# FilterBoard_Schematic.net
KiCad netlist of a schematic drawn in Altium Designer
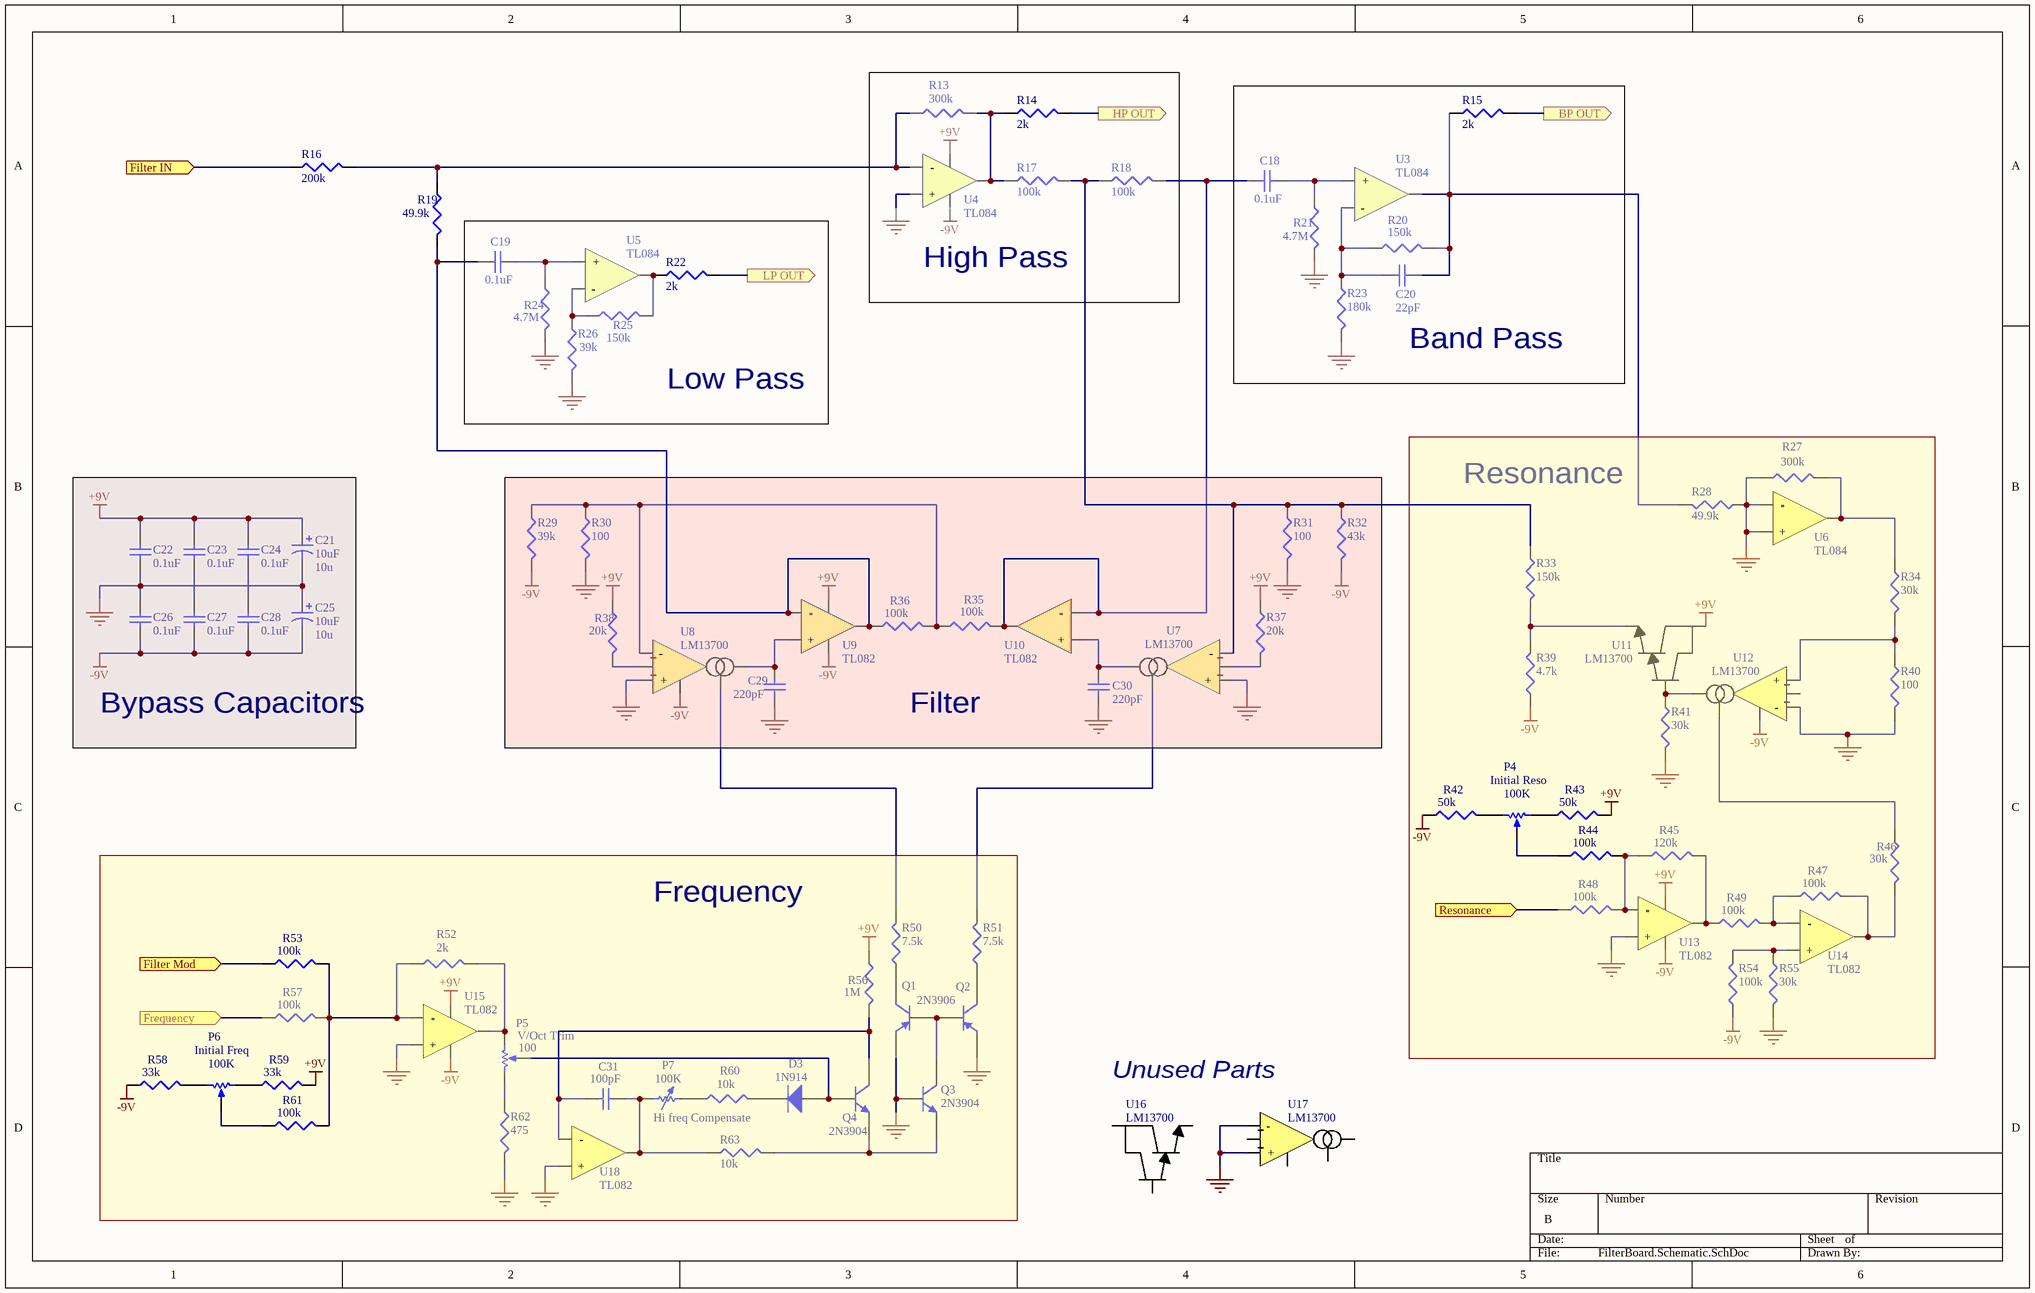
[diagram p0: FilterBoard.Schematic.SchDoc]

(export (version "E")
  (design (tool "Eeschema 10.0.6"))
  (components
    (comp (ref "C18")
      (value "0.1uF")
      (footprint "CAPC1608N")
      (description "Capacitor (Semiconductor SIM Model)")
      (fields (field (name "PUBLISHER") "Altium Limited"))
      (libsource (lib "Miscellaneous Devices") (part "Cap Semi"))
    )
    (comp (ref "C19")
      (value "0.1uF")
      (footprint "CAPC1608N")
      (description "Capacitor (Semiconductor SIM Model)")
      (fields (field (name "PUBLISHER") "Altium Limited"))
      (libsource (lib "Miscellaneous Devices") (part "Cap Semi"))
    )
    (comp (ref "C20")
      (value "22pF")
      (footprint "CAPC1608N")
      (description "Capacitor (Semiconductor SIM Model)")
      (fields (field (name "PUBLISHER") "Altium Limited"))
      (libsource (lib "Miscellaneous Devices") (part "Cap Semi"))
    )
    (comp (ref "C21")
      (value "10uF")
      (footprint "RB7.6-15")
      (description "Polarized Capacitor (Radial)")
      (fields (field (name "ALTIUM_VALUE") "10u") (field (name "PUBLISHER") "Altium Limited"))
      (libsource (lib "Miscellaneous Devices") (part "Cap Pol1"))
    )
    (comp (ref "C22")
      (value "0.1uF")
      (footprint "CAPC1608N")
      (description "Capacitor (Semiconductor SIM Model)")
      (fields (field (name "PUBLISHER") "Altium Limited"))
      (libsource (lib "Miscellaneous Devices") (part "Cap Semi"))
    )
    (comp (ref "C23")
      (value "0.1uF")
      (footprint "CAPC1608N")
      (description "Capacitor (Semiconductor SIM Model)")
      (fields (field (name "PUBLISHER") "Altium Limited"))
      (libsource (lib "Miscellaneous Devices") (part "Cap Semi"))
    )
    (comp (ref "C24")
      (value "0.1uF")
      (footprint "CAPC1608N")
      (description "Capacitor (Semiconductor SIM Model)")
      (fields (field (name "PUBLISHER") "Altium Limited"))
      (libsource (lib "Miscellaneous Devices") (part "Cap Semi"))
    )
    (comp (ref "C25")
      (value "10uF")
      (footprint "RB7.6-15")
      (description "Polarized Capacitor (Radial)")
      (fields (field (name "ALTIUM_VALUE") "10u") (field (name "PUBLISHER") "Altium Limited"))
      (libsource (lib "Miscellaneous Devices") (part "Cap Pol1"))
    )
    (comp (ref "C26")
      (value "0.1uF")
      (footprint "CAPC1608N")
      (description "Capacitor (Semiconductor SIM Model)")
      (fields (field (name "PUBLISHER") "Altium Limited"))
      (libsource (lib "Miscellaneous Devices") (part "Cap Semi"))
    )
    (comp (ref "C27")
      (value "0.1uF")
      (footprint "CAPC1608N")
      (description "Capacitor (Semiconductor SIM Model)")
      (fields (field (name "PUBLISHER") "Altium Limited"))
      (libsource (lib "Miscellaneous Devices") (part "Cap Semi"))
    )
    (comp (ref "C28")
      (value "0.1uF")
      (footprint "CAPC1608N")
      (description "Capacitor (Semiconductor SIM Model)")
      (fields (field (name "PUBLISHER") "Altium Limited"))
      (libsource (lib "Miscellaneous Devices") (part "Cap Semi"))
    )
    (comp (ref "C29")
      (value "220pF")
      (footprint "CAPC1608N")
      (description "Capacitor (Semiconductor SIM Model)")
      (fields (field (name "PUBLISHER") "Altium Limited"))
      (libsource (lib "Miscellaneous Devices") (part "Cap Semi"))
    )
    (comp (ref "C30")
      (value "220pF")
      (footprint "CAPC1608N")
      (description "Capacitor (Semiconductor SIM Model)")
      (fields (field (name "PUBLISHER") "Altium Limited"))
      (libsource (lib "Miscellaneous Devices") (part "Cap Semi"))
    )
    (comp (ref "C31")
      (value "100pF")
      (footprint "CAPC1608N")
      (description "Capacitor (Semiconductor SIM Model)")
      (fields (field (name "PUBLISHER") "Altium Limited"))
      (libsource (lib "Miscellaneous Devices") (part "Cap Semi"))
    )
    (comp (ref "D3")
      (value "1N914")
      (footprint "1N914")
      (description "1 Amp General Purpose Rectifier")
      (fields (field (name "PUBLISHER") "Altium Limited"))
      (libsource (lib "Miscellaneous Devices") (part "Diode 1N4001"))
    )
    (comp (ref "P4")
      (value "Initial Reso")
      (footprint "VR5")
      (description "Potentiometer")
      (fields (field (name "ALTIUM_VALUE") "100K") (field (name "PUBLISHER") "Altium Limited"))
      (libsource (lib "Miscellaneous Devices") (part "RPot"))
    )
    (comp (ref "P5")
      (value "V/Oct Trim")
      (footprint "VR5")
      (description "Potentiometer")
      (fields (field (name "ALTIUM_VALUE") "100") (field (name "PUBLISHER") "Altium Limited"))
      (libsource (lib "Miscellaneous Devices") (part "RPot"))
    )
    (comp (ref "P6")
      (value "Initial Freq")
      (footprint "VR5")
      (description "Potentiometer")
      (fields (field (name "ALTIUM_VALUE") "100K") (field (name "PUBLISHER") "Altium Limited"))
      (libsource (lib "Miscellaneous Devices") (part "RPot"))
    )
    (comp (ref "P7")
      (value "Hi freq Compensate")
      (footprint "CAPC1608N")
      (description "Variable Resistor")
      (fields (field (name "ALTIUM_VALUE") "100K") (field (name "PUBLISHER") "Altium Limited"))
      (libsource (lib "Miscellaneous Devices") (part "Res Adj1"))
    )
    (comp (ref "Q1")
      (value "2N3906")
      (footprint "2N3906")
      (description "PNP General Purpose Amplifier")
      (fields (field (name "PUBLISHER") "Altium Limited"))
      (libsource (lib "Miscellaneous Devices") (part "2N3906"))
    )
    (comp (ref "Q2")
      (value "2N3906")
      (footprint "2N3906")
      (description "PNP General Purpose Amplifier")
      (fields (field (name "PUBLISHER") "Altium Limited"))
      (libsource (lib "Miscellaneous Devices") (part "2N3906"))
    )
    (comp (ref "Q3")
      (value "2N3904")
      (footprint "TO-92A")
      (description "NPN General Purpose Amplifier")
      (fields (field (name "PUBLISHER") "Altium Limited"))
      (libsource (lib "Miscellaneous Devices") (part "2N3904"))
    )
    (comp (ref "Q4")
      (value "2N3904")
      (footprint "TO-92A")
      (description "NPN General Purpose Amplifier")
      (fields (field (name "PUBLISHER") "Altium Limited"))
      (libsource (lib "Miscellaneous Devices") (part "2N3904"))
    )
    (comp (ref "R13")
      (value "300k")
      (footprint "CAPC1608N")
      (description "Resistor")
      (fields (field (name "PUBLISHER") "Altium Limited"))
      (libsource (lib "Miscellaneous Devices") (part "Res3"))
    )
    (comp (ref "R14")
      (value "2k")
      (footprint "CAPC1608N")
      (description "Resistor")
      (fields (field (name "PUBLISHER") "Altium Limited"))
      (libsource (lib "Miscellaneous Devices") (part "Res3"))
    )
    (comp (ref "R15")
      (value "2k")
      (footprint "CAPC1608N")
      (description "Resistor")
      (fields (field (name "PUBLISHER") "Altium Limited"))
      (libsource (lib "Miscellaneous Devices") (part "Res3"))
    )
    (comp (ref "R16")
      (value "200k")
      (footprint "CAPC1608N")
      (description "Resistor")
      (fields (field (name "PUBLISHER") "Altium Limited"))
      (libsource (lib "Miscellaneous Devices") (part "Res3"))
    )
    (comp (ref "R17")
      (value "100k")
      (footprint "CAPC1608N")
      (description "Resistor")
      (fields (field (name "PUBLISHER") "Altium Limited"))
      (libsource (lib "Miscellaneous Devices") (part "Res3"))
    )
    (comp (ref "R18")
      (value "100k")
      (footprint "CAPC1608N")
      (description "Resistor")
      (fields (field (name "PUBLISHER") "Altium Limited"))
      (libsource (lib "Miscellaneous Devices") (part "Res3"))
    )
    (comp (ref "R19")
      (value "49.9k")
      (footprint "CAPC1608N")
      (description "Resistor")
      (fields (field (name "PUBLISHER") "Altium Limited"))
      (libsource (lib "Miscellaneous Devices") (part "Res3"))
    )
    (comp (ref "R20")
      (value "150k")
      (footprint "CAPC1608N")
      (description "Resistor")
      (fields (field (name "PUBLISHER") "Altium Limited"))
      (libsource (lib "Miscellaneous Devices") (part "Res3"))
    )
    (comp (ref "R21")
      (value "4.7M")
      (footprint "CAPC1608N")
      (description "Resistor")
      (fields (field (name "PUBLISHER") "Altium Limited"))
      (libsource (lib "Miscellaneous Devices") (part "Res3"))
    )
    (comp (ref "R22")
      (value "2k")
      (footprint "CAPC1608N")
      (description "Resistor")
      (fields (field (name "PUBLISHER") "Altium Limited"))
      (libsource (lib "Miscellaneous Devices") (part "Res3"))
    )
    (comp (ref "R23")
      (value "180k")
      (footprint "CAPC1608N")
      (description "Resistor")
      (fields (field (name "PUBLISHER") "Altium Limited"))
      (libsource (lib "Miscellaneous Devices") (part "Res3"))
    )
    (comp (ref "R24")
      (value "4.7M")
      (footprint "CAPC1608N")
      (description "Resistor")
      (fields (field (name "PUBLISHER") "Altium Limited"))
      (libsource (lib "Miscellaneous Devices") (part "Res3"))
    )
    (comp (ref "R25")
      (value "150k")
      (footprint "CAPC1608N")
      (description "Resistor")
      (fields (field (name "PUBLISHER") "Altium Limited"))
      (libsource (lib "Miscellaneous Devices") (part "Res3"))
    )
    (comp (ref "R26")
      (value "39k")
      (footprint "CAPC1608N")
      (description "Resistor")
      (fields (field (name "PUBLISHER") "Altium Limited"))
      (libsource (lib "Miscellaneous Devices") (part "Res3"))
    )
    (comp (ref "R27")
      (value "300k")
      (footprint "CAPC1608N")
      (description "Resistor")
      (fields (field (name "PUBLISHER") "Altium Limited"))
      (libsource (lib "Miscellaneous Devices") (part "Res3"))
    )
    (comp (ref "R28")
      (value "49.9k")
      (footprint "CAPC1608N")
      (description "Resistor")
      (fields (field (name "PUBLISHER") "Altium Limited"))
      (libsource (lib "Miscellaneous Devices") (part "Res3"))
    )
    (comp (ref "R29")
      (value "39k")
      (footprint "CAPC1608N")
      (description "Resistor")
      (fields (field (name "PUBLISHER") "Altium Limited"))
      (libsource (lib "Miscellaneous Devices") (part "Res3"))
    )
    (comp (ref "R30")
      (value "100")
      (footprint "CAPC1608N")
      (description "Resistor")
      (fields (field (name "PUBLISHER") "Altium Limited"))
      (libsource (lib "Miscellaneous Devices") (part "Res3"))
    )
    (comp (ref "R31")
      (value "100")
      (footprint "CAPC1608N")
      (description "Resistor")
      (fields (field (name "PUBLISHER") "Altium Limited"))
      (libsource (lib "Miscellaneous Devices") (part "Res3"))
    )
    (comp (ref "R32")
      (value "43k")
      (footprint "CAPC1608N")
      (description "Resistor")
      (fields (field (name "PUBLISHER") "Altium Limited"))
      (libsource (lib "Miscellaneous Devices") (part "Res3"))
    )
    (comp (ref "R33")
      (value "150k")
      (footprint "CAPC1608N")
      (description "Resistor")
      (fields (field (name "PUBLISHER") "Altium Limited"))
      (libsource (lib "Miscellaneous Devices") (part "Res3"))
    )
    (comp (ref "R34")
      (value "30k")
      (footprint "CAPC1608N")
      (description "Resistor")
      (fields (field (name "PUBLISHER") "Altium Limited"))
      (libsource (lib "Miscellaneous Devices") (part "Res3"))
    )
    (comp (ref "R35")
      (value "100k")
      (footprint "CAPC1608N")
      (description "Resistor")
      (fields (field (name "PUBLISHER") "Altium Limited"))
      (libsource (lib "Miscellaneous Devices") (part "Res3"))
    )
    (comp (ref "R36")
      (value "100k")
      (footprint "CAPC1608N")
      (description "Resistor")
      (fields (field (name "PUBLISHER") "Altium Limited"))
      (libsource (lib "Miscellaneous Devices") (part "Res3"))
    )
    (comp (ref "R37")
      (value "20k")
      (footprint "CAPC1608N")
      (description "Resistor")
      (fields (field (name "PUBLISHER") "Altium Limited"))
      (libsource (lib "Miscellaneous Devices") (part "Res3"))
    )
    (comp (ref "R38")
      (value "20k")
      (footprint "CAPC1608N")
      (description "Resistor")
      (fields (field (name "PUBLISHER") "Altium Limited"))
      (libsource (lib "Miscellaneous Devices") (part "Res3"))
    )
    (comp (ref "R39")
      (value "4.7k")
      (footprint "CAPC1608N")
      (description "Resistor")
      (fields (field (name "PUBLISHER") "Altium Limited"))
      (libsource (lib "Miscellaneous Devices") (part "Res3"))
    )
    (comp (ref "R40")
      (value "100")
      (footprint "CAPC1608N")
      (description "Resistor")
      (fields (field (name "PUBLISHER") "Altium Limited"))
      (libsource (lib "Miscellaneous Devices") (part "Res3"))
    )
    (comp (ref "R41")
      (value "30k")
      (footprint "CAPC1608N")
      (description "Resistor")
      (fields (field (name "PUBLISHER") "Altium Limited"))
      (libsource (lib "Miscellaneous Devices") (part "Res3"))
    )
    (comp (ref "R42")
      (value "50k")
      (footprint "CAPC1608N")
      (description "Resistor")
      (fields (field (name "PUBLISHER") "Altium Limited"))
      (libsource (lib "Miscellaneous Devices") (part "Res3"))
    )
    (comp (ref "R43")
      (value "50k")
      (footprint "CAPC1608N")
      (description "Resistor")
      (fields (field (name "PUBLISHER") "Altium Limited"))
      (libsource (lib "Miscellaneous Devices") (part "Res3"))
    )
    (comp (ref "R44")
      (value "100k")
      (footprint "CAPC1608N")
      (description "Resistor")
      (fields (field (name "PUBLISHER") "Altium Limited"))
      (libsource (lib "Miscellaneous Devices") (part "Res3"))
    )
    (comp (ref "R45")
      (value "120k")
      (footprint "CAPC1608N")
      (description "Resistor")
      (fields (field (name "PUBLISHER") "Altium Limited"))
      (libsource (lib "Miscellaneous Devices") (part "Res3"))
    )
    (comp (ref "R46")
      (value "30k")
      (footprint "CAPC1608N")
      (description "Resistor")
      (fields (field (name "PUBLISHER") "Altium Limited"))
      (libsource (lib "Miscellaneous Devices") (part "Res3"))
    )
    (comp (ref "R47")
      (value "100k")
      (footprint "CAPC1608N")
      (description "Resistor")
      (fields (field (name "PUBLISHER") "Altium Limited"))
      (libsource (lib "Miscellaneous Devices") (part "Res3"))
    )
    (comp (ref "R48")
      (value "100k")
      (footprint "CAPC1608N")
      (description "Resistor")
      (fields (field (name "PUBLISHER") "Altium Limited"))
      (libsource (lib "Miscellaneous Devices") (part "Res3"))
    )
    (comp (ref "R49")
      (value "100k")
      (footprint "CAPC1608N")
      (description "Resistor")
      (fields (field (name "PUBLISHER") "Altium Limited"))
      (libsource (lib "Miscellaneous Devices") (part "Res3"))
    )
    (comp (ref "R50")
      (value "7.5k")
      (footprint "CAPC1608N")
      (description "Resistor")
      (fields (field (name "PUBLISHER") "Altium Limited"))
      (libsource (lib "Miscellaneous Devices") (part "Res3"))
    )
    (comp (ref "R51")
      (value "7.5k")
      (footprint "CAPC1608N")
      (description "Resistor")
      (fields (field (name "PUBLISHER") "Altium Limited"))
      (libsource (lib "Miscellaneous Devices") (part "Res3"))
    )
    (comp (ref "R52")
      (value "2k")
      (footprint "CAPC1608N")
      (description "Resistor")
      (fields (field (name "PUBLISHER") "Altium Limited"))
      (libsource (lib "Miscellaneous Devices") (part "Res3"))
    )
    (comp (ref "R53")
      (value "100k")
      (footprint "CAPC1608N")
      (description "Resistor")
      (fields (field (name "PUBLISHER") "Altium Limited"))
      (libsource (lib "Miscellaneous Devices") (part "Res3"))
    )
    (comp (ref "R54")
      (value "100k")
      (footprint "CAPC1608N")
      (description "Resistor")
      (fields (field (name "PUBLISHER") "Altium Limited"))
      (libsource (lib "Miscellaneous Devices") (part "Res3"))
    )
    (comp (ref "R55")
      (value "30k")
      (footprint "CAPC1608N")
      (description "Resistor")
      (fields (field (name "PUBLISHER") "Altium Limited"))
      (libsource (lib "Miscellaneous Devices") (part "Res3"))
    )
    (comp (ref "R56")
      (value "1M")
      (footprint "CAPC1608N")
      (description "Resistor")
      (fields (field (name "PUBLISHER") "Altium Limited"))
      (libsource (lib "Miscellaneous Devices") (part "Res3"))
    )
    (comp (ref "R57")
      (value "100k")
      (footprint "CAPC1608N")
      (description "Resistor")
      (fields (field (name "PUBLISHER") "Altium Limited"))
      (libsource (lib "Miscellaneous Devices") (part "Res3"))
    )
    (comp (ref "R58")
      (value "33k")
      (footprint "CAPC1608N")
      (description "Resistor")
      (fields (field (name "PUBLISHER") "Altium Limited"))
      (libsource (lib "Miscellaneous Devices") (part "Res3"))
    )
    (comp (ref "R59")
      (value "33k")
      (footprint "CAPC1608N")
      (description "Resistor")
      (fields (field (name "PUBLISHER") "Altium Limited"))
      (libsource (lib "Miscellaneous Devices") (part "Res3"))
    )
    (comp (ref "R60")
      (value "10k")
      (footprint "CAPC1608N")
      (description "Resistor")
      (fields (field (name "PUBLISHER") "Altium Limited"))
      (libsource (lib "Miscellaneous Devices") (part "Res3"))
    )
    (comp (ref "R61")
      (value "100k")
      (footprint "CAPC1608N")
      (description "Resistor")
      (fields (field (name "PUBLISHER") "Altium Limited"))
      (libsource (lib "Miscellaneous Devices") (part "Res3"))
    )
    (comp (ref "R62")
      (value "475")
      (footprint "CAPC1608N")
      (description "Resistor")
      (fields (field (name "PUBLISHER") "Altium Limited"))
      (libsource (lib "Miscellaneous Devices") (part "Res3"))
    )
    (comp (ref "R63")
      (value "10k")
      (footprint "CAPC1608N")
      (description "Resistor")
      (fields (field (name "PUBLISHER") "Altium Limited"))
      (libsource (lib "Miscellaneous Devices") (part "Res3"))
    )
    (comp (ref "U3") (value "TL084") (libsource (lib "") (part "TL084_1")))
    (comp (ref "U4") (value "TL084") (libsource (lib "SynthyTwo.Components") (part "TL084")))
    (comp (ref "U5") (value "TL084") (libsource (lib "") (part "TL084_1")))
    (comp (ref "U6") (value "TL084") (libsource (lib "") (part "TL084_2")))
    (comp (ref "U7")
      (value "LM13700")
      (footprint "LM13700")
      (libsource (lib "SynthyTwo.Components") (part "LM13700"))
    )
    (comp (ref "U8")
      (value "LM13700")
      (footprint "LM13700")
      (libsource (lib "SynthyTwo.Components") (part "LM13700"))
    )
    (comp (ref "U9")
      (value "TL082")
      (footprint "TL084")
      (libsource (lib "SynthyTwo.Components") (part "TL082"))
    )
    (comp (ref "U10") (value "TL082") (footprint "TL084") (libsource (lib "") (part "TL082_1")))
    (comp (ref "U11") (value "LM13700") (libsource (lib "SynthyTwo.Components") (part "LM13700_1")))
    (comp (ref "U12")
      (value "LM13700")
      (footprint "LM13700")
      (libsource (lib "SynthyTwo.Components") (part "LM13700"))
    )
    (comp (ref "U13")
      (value "TL082")
      (footprint "TL084")
      (libsource (lib "SynthyTwo.Components") (part "TL082"))
    )
    (comp (ref "U14") (value "TL082") (footprint "TL084") (libsource (lib "") (part "TL082_1")))
    (comp (ref "U15")
      (value "TL082")
      (footprint "TL084")
      (libsource (lib "SynthyTwo.Components") (part "TL082"))
    )
    (comp (ref "U16") (value "LM13700") (libsource (lib "SynthyTwo.Components") (part "LM13700_1")))
    (comp (ref "U17")
      (value "LM13700")
      (footprint "LM13700")
      (libsource (lib "SynthyTwo.Components") (part "LM13700"))
    )
    (comp (ref "U18") (value "TL082") (footprint "TL084") (libsource (lib "") (part "TL082_1")))
  )
  (nets
    (net (code "1") (name "+9V") (class "Default")
      (node (ref "C21") (pin "1") (pinfunction "1_1") (pintype "passive"))
      (node (ref "C22") (pin "2") (pinfunction "2_2") (pintype "passive"))
      (node (ref "C23") (pin "2") (pinfunction "2_2") (pintype "passive"))
      (node (ref "C24") (pin "2") (pinfunction "2_2") (pintype "passive"))
      (node (ref "R37") (pin "1") (pinfunction "1_1") (pintype "passive"))
      (node (ref "R38") (pin "1") (pinfunction "1_1") (pintype "passive"))
      (node (ref "R43") (pin "2") (pinfunction "2_2") (pintype "passive"))
      (node (ref "R56") (pin "1") (pinfunction "1_1") (pintype "passive"))
      (node (ref "R59") (pin "2") (pinfunction "2_2") (pintype "passive"))
      (node (ref "U11") (pin "11") (pinfunction "V+_11") (pintype "passive"))
      (node (ref "U13") (pin "8") (pinfunction "VCC+_8") (pintype "passive"))
      (node (ref "U15") (pin "8") (pinfunction "VCC+_8") (pintype "passive"))
      (node (ref "U4") (pin "4") (pinfunction "VCC+_4") (pintype "passive"))
      (node (ref "U9") (pin "8") (pinfunction "VCC+_8") (pintype "passive"))
    )
    (net (code "2") (name "-9V") (class "Default")
      (node (ref "C25") (pin "2") (pinfunction "2_2") (pintype "passive"))
      (node (ref "C26") (pin "1") (pinfunction "1_1") (pintype "passive"))
      (node (ref "C27") (pin "1") (pinfunction "1_1") (pintype "passive"))
      (node (ref "C28") (pin "1") (pinfunction "1_1") (pintype "passive"))
      (node (ref "R29") (pin "2") (pinfunction "2_2") (pintype "passive"))
      (node (ref "R32") (pin "2") (pinfunction "2_2") (pintype "passive"))
      (node (ref "R39") (pin "1") (pinfunction "1_1") (pintype "passive"))
      (node (ref "R42") (pin "1") (pinfunction "1_1") (pintype "passive"))
      (node (ref "R54") (pin "1") (pinfunction "1_1") (pintype "passive"))
      (node (ref "R58") (pin "1") (pinfunction "1_1") (pintype "passive"))
      (node (ref "U12") (pin "6") (pinfunction "VCC-_6") (pintype "passive"))
      (node (ref "U13") (pin "4") (pinfunction "VCC-_4") (pintype "passive"))
      (node (ref "U15") (pin "4") (pinfunction "VCC-_4") (pintype "passive"))
      (node (ref "U4") (pin "11") (pinfunction "VCC-_11") (pintype "passive"))
      (node (ref "U8") (pin "6") (pinfunction "VCC-_6") (pintype "passive"))
      (node (ref "U9") (pin "4") (pinfunction "VCC-_4") (pintype "passive"))
    )
    (net (code "3") (name "/BP OUT") (class "Default")
      (node (ref "R15") (pin "2") (pinfunction "2_2") (pintype "passive"))
    )
    (net (code "4") (name "/Filter IN") (class "Default")
      (node (ref "R16") (pin "1") (pinfunction "1_1") (pintype "passive"))
    )
    (net (code "5") (name "/Filter Mod") (class "Default")
      (node (ref "R53") (pin "1") (pinfunction "1_1") (pintype "passive"))
    )
    (net (code "6") (name "/Frequency") (class "Default")
      (node (ref "R57") (pin "1") (pinfunction "1_1") (pintype "passive"))
    )
    (net (code "7") (name "/HP OUT") (class "Default")
      (node (ref "R14") (pin "2") (pinfunction "2_2") (pintype "passive"))
    )
    (net (code "8") (name "/LP OUT") (class "Default")
      (node (ref "R22") (pin "2") (pinfunction "2_2") (pintype "passive"))
    )
    (net (code "9") (name "/Resonance") (class "Default")
      (node (ref "R48") (pin "1") (pinfunction "1_1") (pintype "passive"))
    )
    (net (code "10") (name "GND") (class "Default")
      (node (ref "C21") (pin "2") (pinfunction "2_2") (pintype "passive"))
      (node (ref "C22") (pin "1") (pinfunction "1_1") (pintype "passive"))
      (node (ref "C25") (pin "1") (pinfunction "1_1") (pintype "passive"))
      (node (ref "C26") (pin "2") (pinfunction "2_2") (pintype "passive"))
      (node (ref "C29") (pin "1") (pinfunction "1_1") (pintype "passive"))
      (node (ref "C30") (pin "1") (pinfunction "1_1") (pintype "passive"))
      (node (ref "Q1") (pin "1") (pinfunction "E_1") (pintype "passive"))
      (node (ref "Q2") (pin "1") (pinfunction "E_1") (pintype "passive"))
      (node (ref "Q3") (pin "2") (pinfunction "B_2") (pintype "passive"))
      (node (ref "R21") (pin "2") (pinfunction "2_2") (pintype "passive"))
      (node (ref "R23") (pin "2") (pinfunction "2_2") (pintype "passive"))
      (node (ref "R24") (pin "2") (pinfunction "2_2") (pintype "passive"))
      (node (ref "R26") (pin "2") (pinfunction "2_2") (pintype "passive"))
      (node (ref "R27") (pin "1") (pinfunction "1_1") (pintype "passive"))
      (node (ref "R28") (pin "1") (pinfunction "1_1") (pintype "passive"))
      (node (ref "R30") (pin "2") (pinfunction "2_2") (pintype "passive"))
      (node (ref "R31") (pin "2") (pinfunction "2_2") (pintype "passive"))
      (node (ref "R40") (pin "2") (pinfunction "2_2") (pintype "passive"))
      (node (ref "R41") (pin "2") (pinfunction "2_2") (pintype "passive"))
      (node (ref "R55") (pin "2") (pinfunction "2_2") (pintype "passive"))
      (node (ref "R62") (pin "2") (pinfunction "2_2") (pintype "passive"))
      (node (ref "U12") (pin "3") (pinfunction "+_3") (pintype "passive"))
      (node (ref "U13") (pin "3") (pinfunction "+_3") (pintype "passive"))
      (node (ref "U15") (pin "3") (pinfunction "+_3") (pintype "passive"))
      (node (ref "U17") (pin "3") (pinfunction "+_3") (pintype "passive"))
      (node (ref "U17") (pin "4") (pinfunction "-_4") (pintype "passive"))
      (node (ref "U18") (pin "5") (pinfunction "+_5") (pintype "passive"))
      (node (ref "U4") (pin "3") (pinfunction "+_3") (pintype "passive"))
      (node (ref "U6") (pin "12") (pinfunction "-_12") (pintype "passive"))
      (node (ref "U6") (pin "13") (pinfunction "+_13") (pintype "passive"))
      (node (ref "U7") (pin "3") (pinfunction "+_3") (pintype "passive"))
      (node (ref "U8") (pin "3") (pinfunction "+_3") (pintype "passive"))
    )
    (net (code "11") (name "Net-(C23-Pad1)") (class "Default")
      (node (ref "C23") (pin "1") (pinfunction "1_1") (pintype "passive"))
      (node (ref "C27") (pin "2") (pinfunction "2_2") (pintype "passive"))
    )
    (net (code "12") (name "Net-(C24-Pad1)") (class "Default")
      (node (ref "C24") (pin "1") (pinfunction "1_1") (pintype "passive"))
      (node (ref "C28") (pin "2") (pinfunction "2_2") (pintype "passive"))
    )
    (net (code "13") (name "Net-(D3-A)") (class "Default")
      (node (ref "D3") (pin "1") (pinfunction "A_1") (pintype "passive"))
      (node (ref "P5") (pin "3") (pinfunction "TAP_3") (pintype "passive"))
      (node (ref "Q4") (pin "2") (pinfunction "B_2") (pintype "passive"))
    )
    (net (code "14") (name "Net-(D3-K)") (class "Default")
      (node (ref "D3") (pin "2") (pinfunction "K_2") (pintype "passive"))
      (node (ref "R60") (pin "2") (pinfunction "2_2") (pintype "passive"))
    )
    (net (code "15") (name "Net-(P4-BOT)") (class "Default")
      (node (ref "P4") (pin "2") (pinfunction "BOT_2") (pintype "passive"))
      (node (ref "R42") (pin "2") (pinfunction "2_2") (pintype "passive"))
    )
    (net (code "16") (name "Net-(P4-TAP)") (class "Default")
      (node (ref "P4") (pin "3") (pinfunction "TAP_3") (pintype "passive"))
      (node (ref "R44") (pin "1") (pinfunction "1_1") (pintype "passive"))
    )
    (net (code "17") (name "Net-(P4-TOP)") (class "Default")
      (node (ref "P4") (pin "1") (pinfunction "TOP_1") (pintype "passive"))
      (node (ref "R43") (pin "1") (pinfunction "1_1") (pintype "passive"))
    )
    (net (code "18") (name "Net-(P5-BOT)") (class "Default")
      (node (ref "P5") (pin "2") (pinfunction "BOT_2") (pintype "passive"))
      (node (ref "R62") (pin "1") (pinfunction "1_1") (pintype "passive"))
    )
    (net (code "19") (name "Net-(P5-TOP)") (class "Default")
      (node (ref "P5") (pin "1") (pinfunction "TOP_1") (pintype "passive"))
      (node (ref "R52") (pin "2") (pinfunction "2_2") (pintype "passive"))
      (node (ref "U15") (pin "1") (pinfunction "OUT_1") (pintype "passive"))
    )
    (net (code "20") (name "Net-(P6-BOT)") (class "Default")
      (node (ref "P6") (pin "2") (pinfunction "BOT_2") (pintype "passive"))
      (node (ref "R58") (pin "2") (pinfunction "2_2") (pintype "passive"))
    )
    (net (code "21") (name "Net-(P6-TAP)") (class "Default")
      (node (ref "P6") (pin "3") (pinfunction "TAP_3") (pintype "passive"))
      (node (ref "R61") (pin "1") (pinfunction "1_1") (pintype "passive"))
    )
    (net (code "22") (name "Net-(P6-TOP)") (class "Default")
      (node (ref "P6") (pin "1") (pinfunction "TOP_1") (pintype "passive"))
      (node (ref "R59") (pin "1") (pinfunction "1_1") (pintype "passive"))
    )
    (net (code "23") (name "Net-(P7-Pad2)") (class "Default")
      (node (ref "P7") (pin "2") (pinfunction "2_2") (pintype "passive"))
      (node (ref "R60") (pin "1") (pinfunction "1_1") (pintype "passive"))
    )
    (net (code "24") (name "Net-(Q1-B)") (class "Default")
      (node (ref "Q1") (pin "2") (pinfunction "B_2") (pintype "passive"))
      (node (ref "Q2") (pin "2") (pinfunction "B_2") (pintype "passive"))
      (node (ref "Q3") (pin "3") (pinfunction "C_3") (pintype "passive"))
    )
    (net (code "25") (name "Net-(Q1-C)") (class "Default")
      (node (ref "Q1") (pin "3") (pinfunction "C_3") (pintype "passive"))
      (node (ref "R50") (pin "1") (pinfunction "1_1") (pintype "passive"))
    )
    (net (code "26") (name "Net-(Q2-C)") (class "Default")
      (node (ref "Q2") (pin "3") (pinfunction "C_3") (pintype "passive"))
      (node (ref "R51") (pin "1") (pinfunction "1_1") (pintype "passive"))
    )
    (net (code "27") (name "Net-(Q3-E)") (class "Default")
      (node (ref "Q3") (pin "1") (pinfunction "E_1") (pintype "passive"))
      (node (ref "Q4") (pin "1") (pinfunction "E_1") (pintype "passive"))
      (node (ref "R63") (pin "2") (pinfunction "2_2") (pintype "passive"))
    )
    (net (code "28") (name "Net-(Q4-C)") (class "Default")
      (node (ref "C31") (pin "1") (pinfunction "1_1") (pintype "passive"))
      (node (ref "Q4") (pin "3") (pinfunction "C_3") (pintype "passive"))
      (node (ref "R56") (pin "2") (pinfunction "2_2") (pintype "passive"))
      (node (ref "U18") (pin "6") (pinfunction "-_6") (pintype "passive"))
    )
    (net (code "29") (name "Net-(R37-Pad2)") (class "Default")
      (node (ref "R37") (pin "2") (pinfunction "2_2") (pintype "passive"))
      (node (ref "U7") (pin "2") (pinfunction "2_2") (pintype "passive"))
    )
    (net (code "30") (name "Net-(R38-Pad2)") (class "Default")
      (node (ref "R38") (pin "2") (pinfunction "2_2") (pintype "passive"))
      (node (ref "U8") (pin "2") (pinfunction "2_2") (pintype "passive"))
    )
    (net (code "31") (name "Net-(U3-+)") (class "Default")
      (node (ref "C18") (pin "2") (pinfunction "2_2") (pintype "passive"))
      (node (ref "R21") (pin "1") (pinfunction "1_1") (pintype "passive"))
      (node (ref "U3") (pin "5") (pinfunction "+_5") (pintype "passive"))
    )
    (net (code "32") (name "Net-(U3--)") (class "Default")
      (node (ref "C20") (pin "1") (pinfunction "1_1") (pintype "passive"))
      (node (ref "R20") (pin "1") (pinfunction "1_1") (pintype "passive"))
      (node (ref "R23") (pin "1") (pinfunction "1_1") (pintype "passive"))
      (node (ref "U3") (pin "3") (pinfunction "-_3") (pintype "passive"))
    )
    (net (code "33") (name "Net-(U3-OUT)") (class "Default")
      (node (ref "C20") (pin "2") (pinfunction "2_2") (pintype "passive"))
      (node (ref "R15") (pin "1") (pinfunction "1_1") (pintype "passive"))
      (node (ref "R20") (pin "2") (pinfunction "2_2") (pintype "passive"))
      (node (ref "R28") (pin "2") (pinfunction "2_2") (pintype "passive"))
      (node (ref "U3") (pin "7") (pinfunction "OUT_7") (pintype "passive"))
    )
    (net (code "34") (name "Net-(U4--)") (class "Default")
      (node (ref "R13") (pin "1") (pinfunction "1_1") (pintype "passive"))
      (node (ref "R16") (pin "2") (pinfunction "2_2") (pintype "passive"))
      (node (ref "R19") (pin "1") (pinfunction "1_1") (pintype "passive"))
      (node (ref "U4") (pin "2") (pinfunction "-_2") (pintype "passive"))
    )
    (net (code "35") (name "Net-(U4-OUT)") (class "Default")
      (node (ref "R13") (pin "2") (pinfunction "2_2") (pintype "passive"))
      (node (ref "R14") (pin "1") (pinfunction "1_1") (pintype "passive"))
      (node (ref "R17") (pin "1") (pinfunction "1_1") (pintype "passive"))
      (node (ref "U4") (pin "1") (pinfunction "OUT_1") (pintype "passive"))
    )
    (net (code "36") (name "Net-(U5-+)") (class "Default")
      (node (ref "C19") (pin "2") (pinfunction "2_2") (pintype "passive"))
      (node (ref "R24") (pin "1") (pinfunction "1_1") (pintype "passive"))
      (node (ref "U5") (pin "5") (pinfunction "+_5") (pintype "passive"))
    )
    (net (code "37") (name "Net-(U5--)") (class "Default")
      (node (ref "R25") (pin "1") (pinfunction "1_1") (pintype "passive"))
      (node (ref "R26") (pin "1") (pinfunction "1_1") (pintype "passive"))
      (node (ref "U5") (pin "3") (pinfunction "-_3") (pintype "passive"))
    )
    (net (code "38") (name "Net-(U5-OUT)") (class "Default")
      (node (ref "R22") (pin "1") (pinfunction "1_1") (pintype "passive"))
      (node (ref "R25") (pin "2") (pinfunction "2_2") (pintype "passive"))
      (node (ref "U5") (pin "7") (pinfunction "OUT_7") (pintype "passive"))
    )
    (net (code "39") (name "Net-(U6-OUT)") (class "Default")
      (node (ref "R27") (pin "2") (pinfunction "2_2") (pintype "passive"))
      (node (ref "R34") (pin "1") (pinfunction "1_1") (pintype "passive"))
      (node (ref "U6") (pin "14") (pinfunction "OUT_14") (pintype "passive"))
    )
    (net (code "40") (name "Net-(U7--)") (class "Default")
      (node (ref "R17") (pin "2") (pinfunction "2_2") (pintype "passive"))
      (node (ref "R18") (pin "1") (pinfunction "1_1") (pintype "passive"))
      (node (ref "R31") (pin "1") (pinfunction "1_1") (pintype "passive"))
      (node (ref "R32") (pin "1") (pinfunction "1_1") (pintype "passive"))
      (node (ref "R33") (pin "1") (pinfunction "1_1") (pintype "passive"))
      (node (ref "U7") (pin "4") (pinfunction "-_4") (pintype "passive"))
    )
    (net (code "41") (name "Net-(U7-BIAS)") (class "Default")
      (node (ref "R51") (pin "2") (pinfunction "2_2") (pintype "passive"))
      (node (ref "U7") (pin "1") (pinfunction "BIAS_1") (pintype "passive"))
    )
    (net (code "42") (name "Net-(U8--)") (class "Default")
      (node (ref "R29") (pin "1") (pinfunction "1_1") (pintype "passive"))
      (node (ref "R30") (pin "1") (pinfunction "1_1") (pintype "passive"))
      (node (ref "R35") (pin "1") (pinfunction "1_1") (pintype "passive"))
      (node (ref "R36") (pin "2") (pinfunction "2_2") (pintype "passive"))
      (node (ref "U8") (pin "4") (pinfunction "-_4") (pintype "passive"))
    )
    (net (code "43") (name "Net-(U8-BIAS)") (class "Default")
      (node (ref "R50") (pin "2") (pinfunction "2_2") (pintype "passive"))
      (node (ref "U8") (pin "1") (pinfunction "BIAS_1") (pintype "passive"))
    )
    (net (code "44") (name "Net-(U8-OUT)") (class "Default")
      (node (ref "C29") (pin "2") (pinfunction "2_2") (pintype "passive"))
      (node (ref "U8") (pin "5") (pinfunction "OUT_5") (pintype "passive"))
      (node (ref "U9") (pin "3") (pinfunction "+_3") (pintype "passive"))
    )
    (net (code "45") (name "Net-(U9--)") (class "Default")
      (node (ref "C19") (pin "1") (pinfunction "1_1") (pintype "passive"))
      (node (ref "R19") (pin "2") (pinfunction "2_2") (pintype "passive"))
      (node (ref "R36") (pin "1") (pinfunction "1_1") (pintype "passive"))
      (node (ref "U9") (pin "1") (pinfunction "OUT_1") (pintype "passive"))
      (node (ref "U9") (pin "2") (pinfunction "-_2") (pintype "passive"))
    )
    (net (code "46") (name "Net-(U10-+)") (class "Default")
      (node (ref "C30") (pin "2") (pinfunction "2_2") (pintype "passive"))
      (node (ref "U10") (pin "5") (pinfunction "+_5") (pintype "passive"))
      (node (ref "U7") (pin "5") (pinfunction "OUT_5") (pintype "passive"))
    )
    (net (code "47") (name "Net-(U10--)") (class "Default")
      (node (ref "C18") (pin "1") (pinfunction "1_1") (pintype "passive"))
      (node (ref "R18") (pin "2") (pinfunction "2_2") (pintype "passive"))
      (node (ref "R35") (pin "2") (pinfunction "2_2") (pintype "passive"))
      (node (ref "U10") (pin "6") (pinfunction "-_6") (pintype "passive"))
      (node (ref "U10") (pin "7") (pinfunction "OUT_7") (pintype "passive"))
    )
    (net (code "48") (name "Net-(U11-BIN)") (class "Default")
      (node (ref "R41") (pin "1") (pinfunction "1_1") (pintype "passive"))
      (node (ref "U11") (pin "7") (pinfunction "BIN_7") (pintype "passive"))
      (node (ref "U12") (pin "5") (pinfunction "OUT_5") (pintype "passive"))
    )
    (net (code "49") (name "Net-(U11-BOUT)") (class "Default")
      (node (ref "R33") (pin "2") (pinfunction "2_2") (pintype "passive"))
      (node (ref "R39") (pin "2") (pinfunction "2_2") (pintype "passive"))
      (node (ref "U11") (pin "8") (pinfunction "BOUT_8") (pintype "passive"))
    )
    (net (code "50") (name "Net-(U12--)") (class "Default")
      (node (ref "R34") (pin "2") (pinfunction "2_2") (pintype "passive"))
      (node (ref "R40") (pin "1") (pinfunction "1_1") (pintype "passive"))
      (node (ref "U12") (pin "4") (pinfunction "-_4") (pintype "passive"))
    )
    (net (code "51") (name "Net-(U12-BIAS)") (class "Default")
      (node (ref "R46") (pin "1") (pinfunction "1_1") (pintype "passive"))
      (node (ref "U12") (pin "1") (pinfunction "BIAS_1") (pintype "passive"))
    )
    (net (code "52") (name "Net-(U13--)") (class "Default")
      (node (ref "R44") (pin "2") (pinfunction "2_2") (pintype "passive"))
      (node (ref "R45") (pin "1") (pinfunction "1_1") (pintype "passive"))
      (node (ref "R48") (pin "2") (pinfunction "2_2") (pintype "passive"))
      (node (ref "U13") (pin "2") (pinfunction "-_2") (pintype "passive"))
    )
    (net (code "53") (name "Net-(U13-OUT)") (class "Default")
      (node (ref "R45") (pin "2") (pinfunction "2_2") (pintype "passive"))
      (node (ref "R49") (pin "1") (pinfunction "1_1") (pintype "passive"))
      (node (ref "U13") (pin "1") (pinfunction "OUT_1") (pintype "passive"))
    )
    (net (code "54") (name "Net-(U14-+)") (class "Default")
      (node (ref "R54") (pin "2") (pinfunction "2_2") (pintype "passive"))
      (node (ref "R55") (pin "1") (pinfunction "1_1") (pintype "passive"))
      (node (ref "U14") (pin "5") (pinfunction "+_5") (pintype "passive"))
    )
    (net (code "55") (name "Net-(U14--)") (class "Default")
      (node (ref "R47") (pin "1") (pinfunction "1_1") (pintype "passive"))
      (node (ref "R49") (pin "2") (pinfunction "2_2") (pintype "passive"))
      (node (ref "U14") (pin "6") (pinfunction "-_6") (pintype "passive"))
    )
    (net (code "56") (name "Net-(U14-OUT)") (class "Default")
      (node (ref "R46") (pin "2") (pinfunction "2_2") (pintype "passive"))
      (node (ref "R47") (pin "2") (pinfunction "2_2") (pintype "passive"))
      (node (ref "U14") (pin "7") (pinfunction "OUT_7") (pintype "passive"))
    )
    (net (code "57") (name "Net-(U15--)") (class "Default")
      (node (ref "R52") (pin "1") (pinfunction "1_1") (pintype "passive"))
      (node (ref "R53") (pin "2") (pinfunction "2_2") (pintype "passive"))
      (node (ref "R57") (pin "2") (pinfunction "2_2") (pintype "passive"))
      (node (ref "R61") (pin "2") (pinfunction "2_2") (pintype "passive"))
      (node (ref "U15") (pin "2") (pinfunction "-_2") (pintype "passive"))
    )
    (net (code "58") (name "Net-(U18-OUT)") (class "Default")
      (node (ref "C31") (pin "2") (pinfunction "2_2") (pintype "passive"))
      (node (ref "P7") (pin "1") (pinfunction "1_1") (pintype "passive"))
      (node (ref "R63") (pin "1") (pinfunction "1_1") (pintype "passive"))
      (node (ref "U18") (pin "7") (pinfunction "OUT_7") (pintype "passive"))
    )
    (net (code "59") (name "unconnected-(U3-VCC+-Pad6)") (class "Default")
      (node (ref "U3") (pin "6") (pinfunction "VCC+_6") (pintype "passive"))
    )
    (net (code "60") (name "unconnected-(U3-VCC--Pad11)") (class "Default")
      (node (ref "U3") (pin "11") (pinfunction "VCC-_11") (pintype "passive"))
    )
    (net (code "61") (name "unconnected-(U5-VCC+-Pad6)") (class "Default")
      (node (ref "U5") (pin "6") (pinfunction "VCC+_6") (pintype "passive"))
    )
    (net (code "62") (name "unconnected-(U5-VCC--Pad11)") (class "Default")
      (node (ref "U5") (pin "11") (pinfunction "VCC-_11") (pintype "passive"))
    )
    (net (code "63") (name "unconnected-(U6-VCC+-Pad1)") (class "Default")
      (node (ref "U6") (pin "1") (pinfunction "VCC+_1") (pintype "passive"))
    )
    (net (code "64") (name "unconnected-(U6-VCC--Pad11)") (class "Default")
      (node (ref "U6") (pin "11") (pinfunction "VCC-_11") (pintype "passive"))
    )
    (net (code "65") (name "unconnected-(U7-VCC--Pad6)") (class "Default")
      (node (ref "U7") (pin "6") (pinfunction "VCC-_6") (pintype "passive"))
    )
    (net (code "66") (name "unconnected-(U10-VCC+-Pad8)") (class "Default")
      (node (ref "U10") (pin "8") (pinfunction "VCC+_8") (pintype "passive"))
    )
    (net (code "67") (name "unconnected-(U10-VCC--Pad4)") (class "Default")
      (node (ref "U10") (pin "4") (pinfunction "VCC-_4") (pintype "passive"))
    )
    (net (code "68") (name "unconnected-(U12-Pad2)") (class "Default")
      (node (ref "U12") (pin "2") (pinfunction "2_2") (pintype "passive"))
    )
    (net (code "69") (name "unconnected-(U14-VCC+-Pad8)") (class "Default")
      (node (ref "U14") (pin "8") (pinfunction "VCC+_8") (pintype "passive"))
    )
    (net (code "70") (name "unconnected-(U14-VCC--Pad4)") (class "Default")
      (node (ref "U14") (pin "4") (pinfunction "VCC-_4") (pintype "passive"))
    )
    (net (code "71") (name "unconnected-(U16-BIN-Pad7)") (class "Default")
      (node (ref "U16") (pin "7") (pinfunction "BIN_7") (pintype "passive"))
    )
    (net (code "72") (name "unconnected-(U16-BOUT-Pad8)") (class "Default")
      (node (ref "U16") (pin "8") (pinfunction "BOUT_8") (pintype "passive"))
    )
    (net (code "73") (name "unconnected-(U16-V+-Pad11)") (class "Default")
      (node (ref "U16") (pin "11") (pinfunction "V+_11") (pintype "passive"))
    )
    (net (code "74") (name "unconnected-(U17-BIAS-Pad1)") (class "Default")
      (node (ref "U17") (pin "1") (pinfunction "BIAS_1") (pintype "passive"))
    )
    (net (code "75") (name "unconnected-(U17-OUT-Pad5)") (class "Default")
      (node (ref "U17") (pin "5") (pinfunction "OUT_5") (pintype "passive"))
    )
    (net (code "76") (name "unconnected-(U17-Pad2)") (class "Default")
      (node (ref "U17") (pin "2") (pinfunction "2_2") (pintype "passive"))
    )
    (net (code "77") (name "unconnected-(U17-VCC--Pad6)") (class "Default")
      (node (ref "U17") (pin "6") (pinfunction "VCC-_6") (pintype "passive"))
    )
    (net (code "78") (name "unconnected-(U18-VCC+-Pad8)") (class "Default")
      (node (ref "U18") (pin "8") (pinfunction "VCC+_8") (pintype "passive"))
    )
    (net (code "79") (name "unconnected-(U18-VCC--Pad4)") (class "Default")
      (node (ref "U18") (pin "4") (pinfunction "VCC-_4") (pintype "passive"))
    )
  )
)
